# Probe.net
KiCad netlist of a schematic drawn in Altium Designer
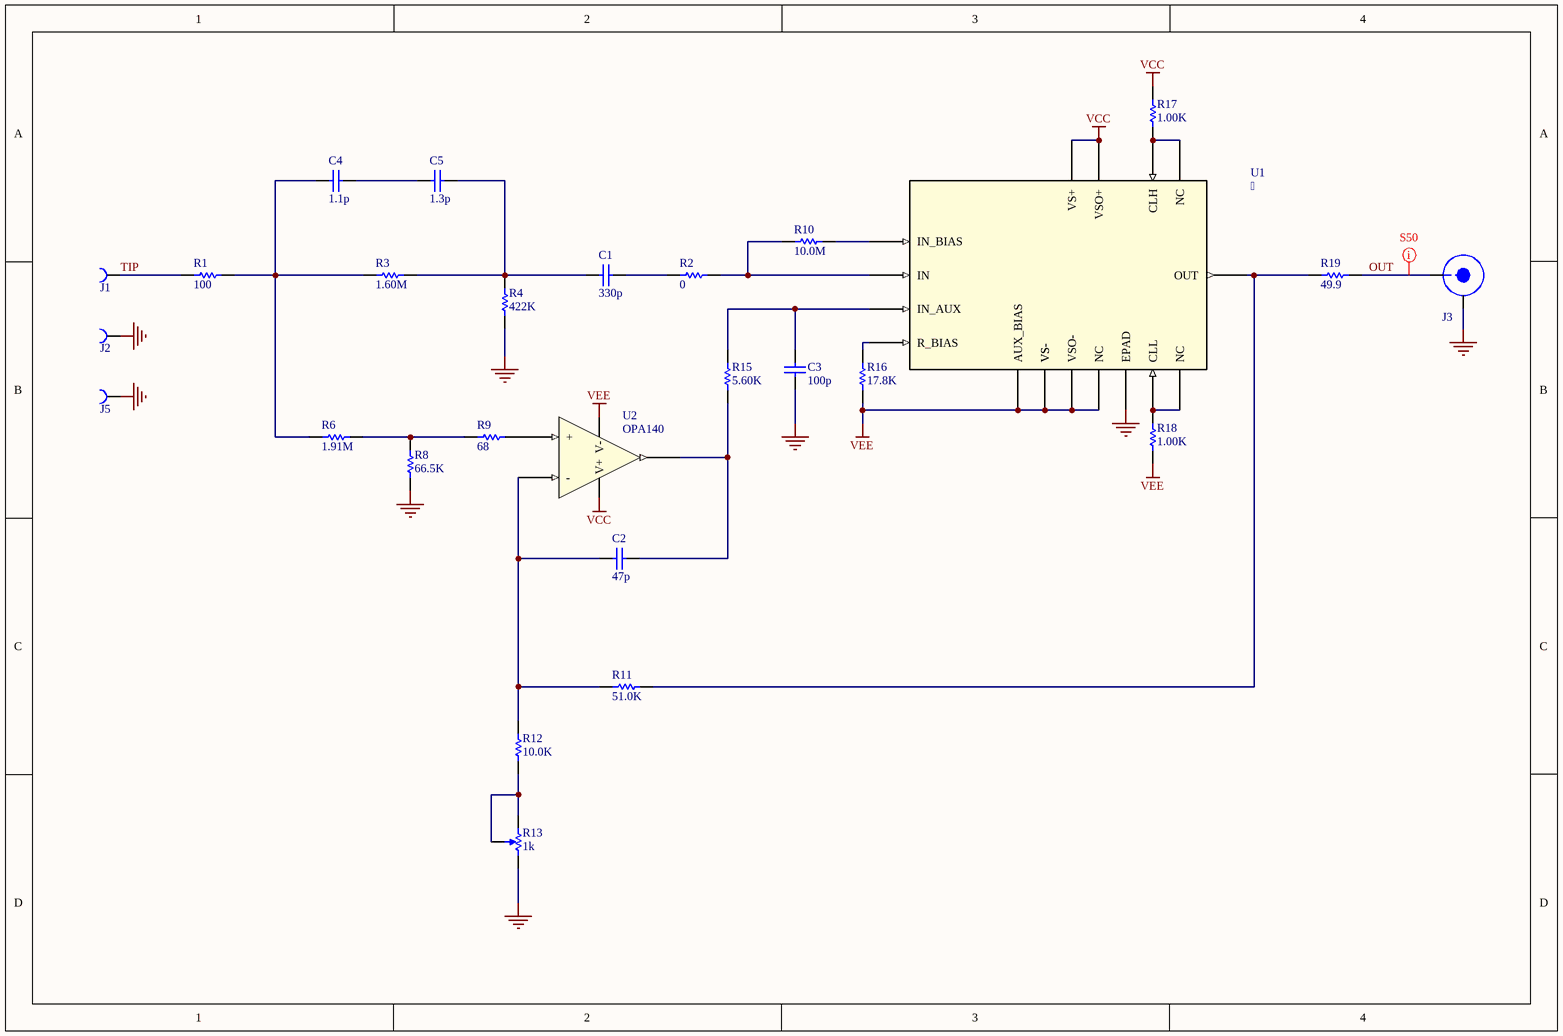
[diagram p0: Probe.SchDoc]

(export (version "E")
  (design (tool "Eeschema 10.0.6"))
  (components
    (comp (ref "C1")
      (value "330p")
      (footprint "CAPC0402(1005)50_M")
      (description "CAP CER 330PF±5% 50V C0G 0402")
      (fields
        (field (name "MANUFACTURER") "Murata")
        (field (name "MANUFACTURER PART NUMBER") "GRM1555C1H331JA01D")
      )
      (libsource (lib "Murata GRM 0402") (part "Capacitor_Generic"))
    )
    (comp (ref "C2")
      (value "47p")
      (footprint "CAPC0402(1005)50_M")
      (description "CAP CER 47PF±5% 50V C0G 0402")
      (fields
        (field (name "MANUFACTURER") "Samsung Electro-Mechanics")
        (field (name "MANUFACTURER PART NUMBER") "CL05C470JB5NNNC")
      )
      (libsource (lib "Samsung CAPC0402") (part "Capacitor_Generic"))
    )
    (comp (ref "C3")
      (value "100p")
      (footprint "CAPC0402(1005)50_M")
      (description "CAP CER 100PF±5% 50V C0G 0402")
      (fields
        (field (name "MANUFACTURER") "Samsung Electro-Mechanics")
        (field (name "MANUFACTURER PART NUMBER") "CL05C101JB5NNNC")
      )
      (libsource (lib "Samsung CAPC0402") (part "Capacitor_Generic"))
    )
    (comp (ref "C4")
      (value "1.1p")
      (footprint "CAPC0402(1005)50_M")
      (description "CAP CER 1.1PF±0.05PF 50V C0G/NP0 0402")
      (fields (field (name "PART NUMBER") "GJM1555C1H1R1WB01") (field (name "TOLERANCE") "±0.05pF"))
      (libsource (lib "Murata GJM 0402") (part "Capacitor_Generic"))
    )
    (comp (ref "C5")
      (value "1.3p")
      (footprint "CAPC0402(1005)50_M")
      (description "CAP CER 1.3PF±0.05PF 50V C0G/NP0 0402")
      (fields (field (name "PART NUMBER") "GJM1555C1H1R3WB01") (field (name "TOLERANCE") "±0.05pF"))
      (libsource (lib "Murata GJM 0402") (part "Capacitor_Generic"))
    )
    (comp (ref "J1")
      (value "0339-0-15-01-15-27-10-0")
      (footprint "MILL-MAX 0339")
      (description "CONN PIN RCPT")
      (fields (field (name "MANUFACTURER") "Mill-Max"))
      (libsource (lib "Connectors") (part "0339-0-15-01-15-27-10-0"))
    )
    (comp (ref "J2")
      (value "0339-0-15-01-15-27-10-0")
      (footprint "MILL-MAX 0339")
      (description "CONN PIN RCPT")
      (fields (field (name "MANUFACTURER") "Mill-Max"))
      (libsource (lib "Connectors") (part "0339-0-15-01-15-27-10-0"))
    )
    (comp (ref "J3")
      (value "901-10511-3")
      (footprint "901-10511-3")
      (description "CONN SMA JACK STR 50OHM EDGE MNT")
      (fields (field (name "MANUFACTURER") "Amphenol RF"))
      (libsource (lib "Connectors") (part "901-10511-3"))
    )
    (comp (ref "J5")
      (value "0339-0-15-01-15-27-10-0")
      (footprint "MILL-MAX 0339")
      (description "CONN PIN RCPT")
      (fields (field (name "MANUFACTURER") "Mill-Max"))
      (libsource (lib "Connectors") (part "0339-0-15-01-15-27-10-0"))
    )
    (comp (ref "R1")
      (value "100")
      (footprint "RESC0402(1005)_M")
      (description "RES 100 OHM 1% 1/16W 0402")
      (fields (field (name "PART NUMBER") "RESC0402-100R-1pct"))
      (libsource (lib "R0402 - 1pct") (part "Resistor_Generic"))
    )
    (comp (ref "R2")
      (value "0")
      (footprint "RESC0402(1005)_M")
      (description "RES 0 OHM JUMPER 0402")
      (fields (field (name "PART NUMBER") "R0402-0R0-JMP"))
      (libsource (lib "R0402 - 1pct") (part "Resistor_Generic"))
    )
    (comp (ref "R3")
      (value "1.60M")
      (footprint "RESC0402(1005)_M")
      (description "RES 1.60M OHM 1% 1/16W 0402")
      (fields (field (name "PART NUMBER") "RESC0402-1M60-1pct"))
      (libsource (lib "R0402 - 1pct") (part "Resistor_Generic"))
    )
    (comp (ref "R4")
      (value "422K")
      (footprint "RESC0402(1005)_M")
      (description "RES 422K OHM 1% 1/16W 0402")
      (fields (field (name "PART NUMBER") "RESC0402-422K-1pct"))
      (libsource (lib "R0402 - 1pct") (part "Resistor_Generic"))
    )
    (comp (ref "R6")
      (value "1.91M")
      (footprint "RESC0402(1005)_M")
      (description "RES 1.91M OHM 1% 1/16W 0402")
      (fields (field (name "PART NUMBER") "RESC0402-1M91-1pct"))
      (libsource (lib "R0402 - 1pct") (part "Resistor_Generic"))
    )
    (comp (ref "R8")
      (value "66.5K")
      (footprint "RESC0402(1005)_M")
      (description "RES 66.5K OHM 1% 1/16W 0402")
      (fields (field (name "PART NUMBER") "RESC0402-66K5-1pct"))
      (libsource (lib "R0402 - 1pct") (part "Resistor_Generic"))
    )
    (comp (ref "R9")
      (value "68")
      (footprint "RESC0402(1005)_M")
      (description "RES 68 OHM 1% 1/16W 0402")
      (fields (field (name "PART NUMBER") "RESC0402-68R0-1pct"))
      (libsource (lib "R0402 - 1pct") (part "Resistor_Generic"))
    )
    (comp (ref "R10")
      (value "10.0M")
      (footprint "RESC0402(1005)_M")
      (description "RES 10.0M OHM 1% 1/16W 0402")
      (fields (field (name "PART NUMBER") "RESC0402-10M0-1pct"))
      (libsource (lib "R0402 - 1pct") (part "Resistor_Generic"))
    )
    (comp (ref "R11")
      (value "51.0K")
      (footprint "RESC0402(1005)_M")
      (description "RES 51.0K OHM 1% 1/16W 0402")
      (fields (field (name "PART NUMBER") "RESC0402-51K0-1pct"))
      (libsource (lib "R0402 - 1pct") (part "Resistor_Generic"))
    )
    (comp (ref "R12")
      (value "10.0K")
      (footprint "RESC0402(1005)_M")
      (description "RES 10.0K OHM 1% 1/16W 0402")
      (fields (field (name "PART NUMBER") "RESC0402-10K0-1pct"))
      (libsource (lib "R0402 - 1pct") (part "Resistor_Generic"))
    )
    (comp (ref "R13")
      (value "1k")
      (footprint "PVG3A")
      (description "TRIMMER 1K OHM 0.25W J LEAD TOP")
      (fields
        (field (name "MANUFACTURER") "Bourns")
        (field (name "MANUFACTURER PART NUMBER") "PVG3A102C01R00")
      )
      (libsource (lib "Trimpots") (part "PVG3A102C01R00"))
    )
    (comp (ref "R15")
      (value "5.60K")
      (footprint "RESC0402(1005)_M")
      (description "RES 5.60K OHM 1% 1/16W 0402")
      (fields (field (name "PART NUMBER") "RESC0402-5K60-1pct"))
      (libsource (lib "R0402 - 1pct") (part "Resistor_Generic"))
    )
    (comp (ref "R16")
      (value "17.8K")
      (footprint "RESC0402(1005)_M")
      (description "RES 17.8K OHM 1% 1/16W 0402")
      (fields (field (name "PART NUMBER") "RESC0402-17K8-1pct"))
      (libsource (lib "R0402 - 1pct") (part "Resistor_Generic"))
    )
    (comp (ref "R17")
      (value "1.00K")
      (footprint "RESC0402(1005)_M")
      (description "RES 1.00K OHM 1% 1/16W 0402")
      (fields (field (name "PART NUMBER") "RESC0402-1K00-1pct"))
      (libsource (lib "R0402 - 1pct") (part "Resistor_Generic"))
    )
    (comp (ref "R18")
      (value "1.00K")
      (footprint "RESC0402(1005)_M")
      (description "RES 1.00K OHM 1% 1/16W 0402")
      (fields (field (name "PART NUMBER") "RESC0402-1K00-1pct"))
      (libsource (lib "R0402 - 1pct") (part "Resistor_Generic"))
    )
    (comp (ref "R19")
      (value "49.9")
      (footprint "RESC0402(1005)_M")
      (description "RES 49.9 OHM 1% 1/16W 0402")
      (fields (field (name "PART NUMBER") "RESC0402-49R9-1pct"))
      (libsource (lib "R0402 - 1pct") (part "Resistor_Generic"))
    )
    (comp (ref "U1")
      (value "")
      (footprint "VQFN16_RGT_TEX- OSHPARK")
      (description "WIDE-BANDWIDTH JFET BUFFER")
      (fields
        (field (name "MANUFACTURER") "Texas Instruments")
        (field (name "MANUFACTURER PART NUMBER") "BUF802IRGTR")
      )
      (libsource (lib "IC") (part "BUF802IRGTR"))
    )
    (comp (ref "U2")
      (value "OPA140")
      (footprint "SOIC-8")
      (description "IC OPAMP JFET 1 CIRCUIT 8SOIC")
      (fields
        (field (name "MANUFACTURER") "Texas Instruments")
        (field (name "MANUFACTURER PART NUMBER") "OPA140AIDR")
      )
      (libsource (lib "IC") (part "OPA140AIDR"))
    )
  )
  (nets
    (net (code "1") (name "/OUT") (class "Default")
      (node (ref "J3") (pin "1") (pinfunction "1_1") (pintype "passive"))
      (node (ref "R19") (pin "2") (pinfunction "2_2") (pintype "passive"))
    )
    (net (code "2") (name "/TIP") (class "Default")
      (node (ref "J1") (pin "1") (pinfunction "1_1") (pintype "passive"))
      (node (ref "R1") (pin "1") (pinfunction "1_1") (pintype "passive"))
    )
    (net (code "3") (name "GND") (class "Default")
      (node (ref "C3") (pin "2") (pinfunction "2_2") (pintype "passive"))
      (node (ref "J2") (pin "1") (pinfunction "1_1") (pintype "passive"))
      (node (ref "J3") (pin "2") (pinfunction "2_2") (pintype "passive"))
      (node (ref "J5") (pin "1") (pinfunction "1_1") (pintype "passive"))
      (node (ref "R13") (pin "3") (pinfunction "3_3") (pintype "passive"))
      (node (ref "R4") (pin "2") (pinfunction "2_2") (pintype "passive"))
      (node (ref "R8") (pin "2") (pinfunction "2_2") (pintype "passive"))
      (node (ref "U1") (pin "17") (pinfunction "EPAD_17") (pintype "passive"))
    )
    (net (code "4") (name "Net-(C1-Pad1)") (class "Default")
      (node (ref "C1") (pin "1") (pinfunction "1_1") (pintype "passive"))
      (node (ref "C5") (pin "2") (pinfunction "2_2") (pintype "passive"))
      (node (ref "R3") (pin "2") (pinfunction "2_2") (pintype "passive"))
      (node (ref "R4") (pin "1") (pinfunction "1_1") (pintype "passive"))
    )
    (net (code "5") (name "Net-(C1-Pad2)") (class "Default")
      (node (ref "C1") (pin "2") (pinfunction "2_2") (pintype "passive"))
      (node (ref "R2") (pin "1") (pinfunction "1_1") (pintype "passive"))
    )
    (net (code "6") (name "Net-(C4-Pad1)") (class "Default")
      (node (ref "C4") (pin "1") (pinfunction "1_1") (pintype "passive"))
      (node (ref "R1") (pin "2") (pinfunction "2_2") (pintype "passive"))
      (node (ref "R3") (pin "1") (pinfunction "1_1") (pintype "passive"))
      (node (ref "R6") (pin "1") (pinfunction "1_1") (pintype "passive"))
    )
    (net (code "7") (name "Net-(C4-Pad2)") (class "Default")
      (node (ref "C4") (pin "2") (pinfunction "2_2") (pintype "passive"))
      (node (ref "C5") (pin "1") (pinfunction "1_1") (pintype "passive"))
    )
    (net (code "8") (name "Net-(R6-Pad2)") (class "Default")
      (node (ref "R6") (pin "2") (pinfunction "2_2") (pintype "passive"))
      (node (ref "R8") (pin "1") (pinfunction "1_1") (pintype "passive"))
      (node (ref "R9") (pin "1") (pinfunction "1_1") (pintype "passive"))
    )
    (net (code "9") (name "Net-(R12-Pad2)") (class "Default")
      (node (ref "R12") (pin "2") (pinfunction "2_2") (pintype "passive"))
      (node (ref "R13") (pin "1") (pinfunction "1_1") (pintype "passive"))
      (node (ref "R13") (pin "2") (pinfunction "2_2") (pintype "passive"))
    )
    (net (code "10") (name "Net-(U1-CLH)") (class "Default")
      (node (ref "R17") (pin "1") (pinfunction "1_1") (pintype "passive"))
      (node (ref "U1") (pin "15") (pinfunction "CLH_15") (pintype "input"))
      (node (ref "U1") (pin "16") (pinfunction "NC_16") (pintype "passive"))
    )
    (net (code "11") (name "Net-(U1-CLL)") (class "Default")
      (node (ref "R18") (pin "1") (pinfunction "1_1") (pintype "passive"))
      (node (ref "U1") (pin "13") (pinfunction "NC_13") (pintype "passive"))
      (node (ref "U1") (pin "14") (pinfunction "CLL_14") (pintype "input"))
    )
    (net (code "12") (name "Net-(U1-IN)") (class "Default")
      (node (ref "R10") (pin "1") (pinfunction "1_1") (pintype "passive"))
      (node (ref "R2") (pin "2") (pinfunction "2_2") (pintype "passive"))
      (node (ref "U1") (pin "2") (pinfunction "IN_2") (pintype "input"))
    )
    (net (code "13") (name "Net-(U1-IN_AUX)") (class "Default")
      (node (ref "C3") (pin "1") (pinfunction "1_1") (pintype "passive"))
      (node (ref "R15") (pin "1") (pinfunction "1_1") (pintype "passive"))
      (node (ref "U1") (pin "4") (pinfunction "IN_AUX_4") (pintype "input"))
    )
    (net (code "14") (name "Net-(U1-IN_BIAS)") (class "Default")
      (node (ref "R10") (pin "2") (pinfunction "2_2") (pintype "passive"))
      (node (ref "U1") (pin "3") (pinfunction "IN_BIAS_3") (pintype "input"))
    )
    (net (code "15") (name "Net-(U1-OUT)") (class "Default")
      (node (ref "R11") (pin "2") (pinfunction "2_2") (pintype "passive"))
      (node (ref "R19") (pin "1") (pinfunction "1_1") (pintype "passive"))
      (node (ref "U1") (pin "11") (pinfunction "OUT_11") (pintype "output"))
    )
    (net (code "16") (name "Net-(U1-R_BIAS)") (class "Default")
      (node (ref "R16") (pin "1") (pinfunction "1_1") (pintype "passive"))
      (node (ref "U1") (pin "7") (pinfunction "R_BIAS_7") (pintype "input"))
    )
    (net (code "17") (name "Net-(U2-+)") (class "Default")
      (node (ref "R9") (pin "2") (pinfunction "2_2") (pintype "passive"))
      (node (ref "U2") (pin "3") (pinfunction "+_3") (pintype "input"))
    )
    (net (code "18") (name "Net-(U2--)") (class "Default")
      (node (ref "C2") (pin "1") (pinfunction "1_1") (pintype "passive"))
      (node (ref "R11") (pin "1") (pinfunction "1_1") (pintype "passive"))
      (node (ref "R12") (pin "1") (pinfunction "1_1") (pintype "passive"))
      (node (ref "U2") (pin "2") (pinfunction "-_2") (pintype "input"))
    )
    (net (code "19") (name "Net-(U2-OUT)") (class "Default")
      (node (ref "C2") (pin "2") (pinfunction "2_2") (pintype "passive"))
      (node (ref "R15") (pin "2") (pinfunction "2_2") (pintype "passive"))
      (node (ref "U2") (pin "6") (pinfunction "OUT_6") (pintype "output"))
    )
    (net (code "20") (name "VCC") (class "Default")
      (node (ref "R17") (pin "2") (pinfunction "2_2") (pintype "passive"))
      (node (ref "U1") (pin "1") (pinfunction "VS+_1") (pintype "power_in"))
      (node (ref "U1") (pin "12") (pinfunction "VSO+_12") (pintype "power_in"))
      (node (ref "U2") (pin "7") (pinfunction "V+_7") (pintype "power_in"))
    )
    (net (code "21") (name "VEE") (class "Default")
      (node (ref "R16") (pin "2") (pinfunction "2_2") (pintype "passive"))
      (node (ref "R18") (pin "2") (pinfunction "2_2") (pintype "passive"))
      (node (ref "U1") (pin "10") (pinfunction "VSO-_10") (pintype "power_in"))
      (node (ref "U1") (pin "5") (pinfunction "VS-_5") (pintype "power_in"))
      (node (ref "U1") (pin "6") (pinfunction "AUX_BIAS_6") (pintype "power_in"))
      (node (ref "U1") (pin "8") (pinfunction "VS-_8") (pintype "power_in"))
      (node (ref "U1") (pin "9") (pinfunction "NC_9") (pintype "passive"))
      (node (ref "U2") (pin "4") (pinfunction "V-_4") (pintype "power_in"))
    )
  )
)
